# trezor_v1_1.net
KiCad netlist of a schematic drawn in EAGLE
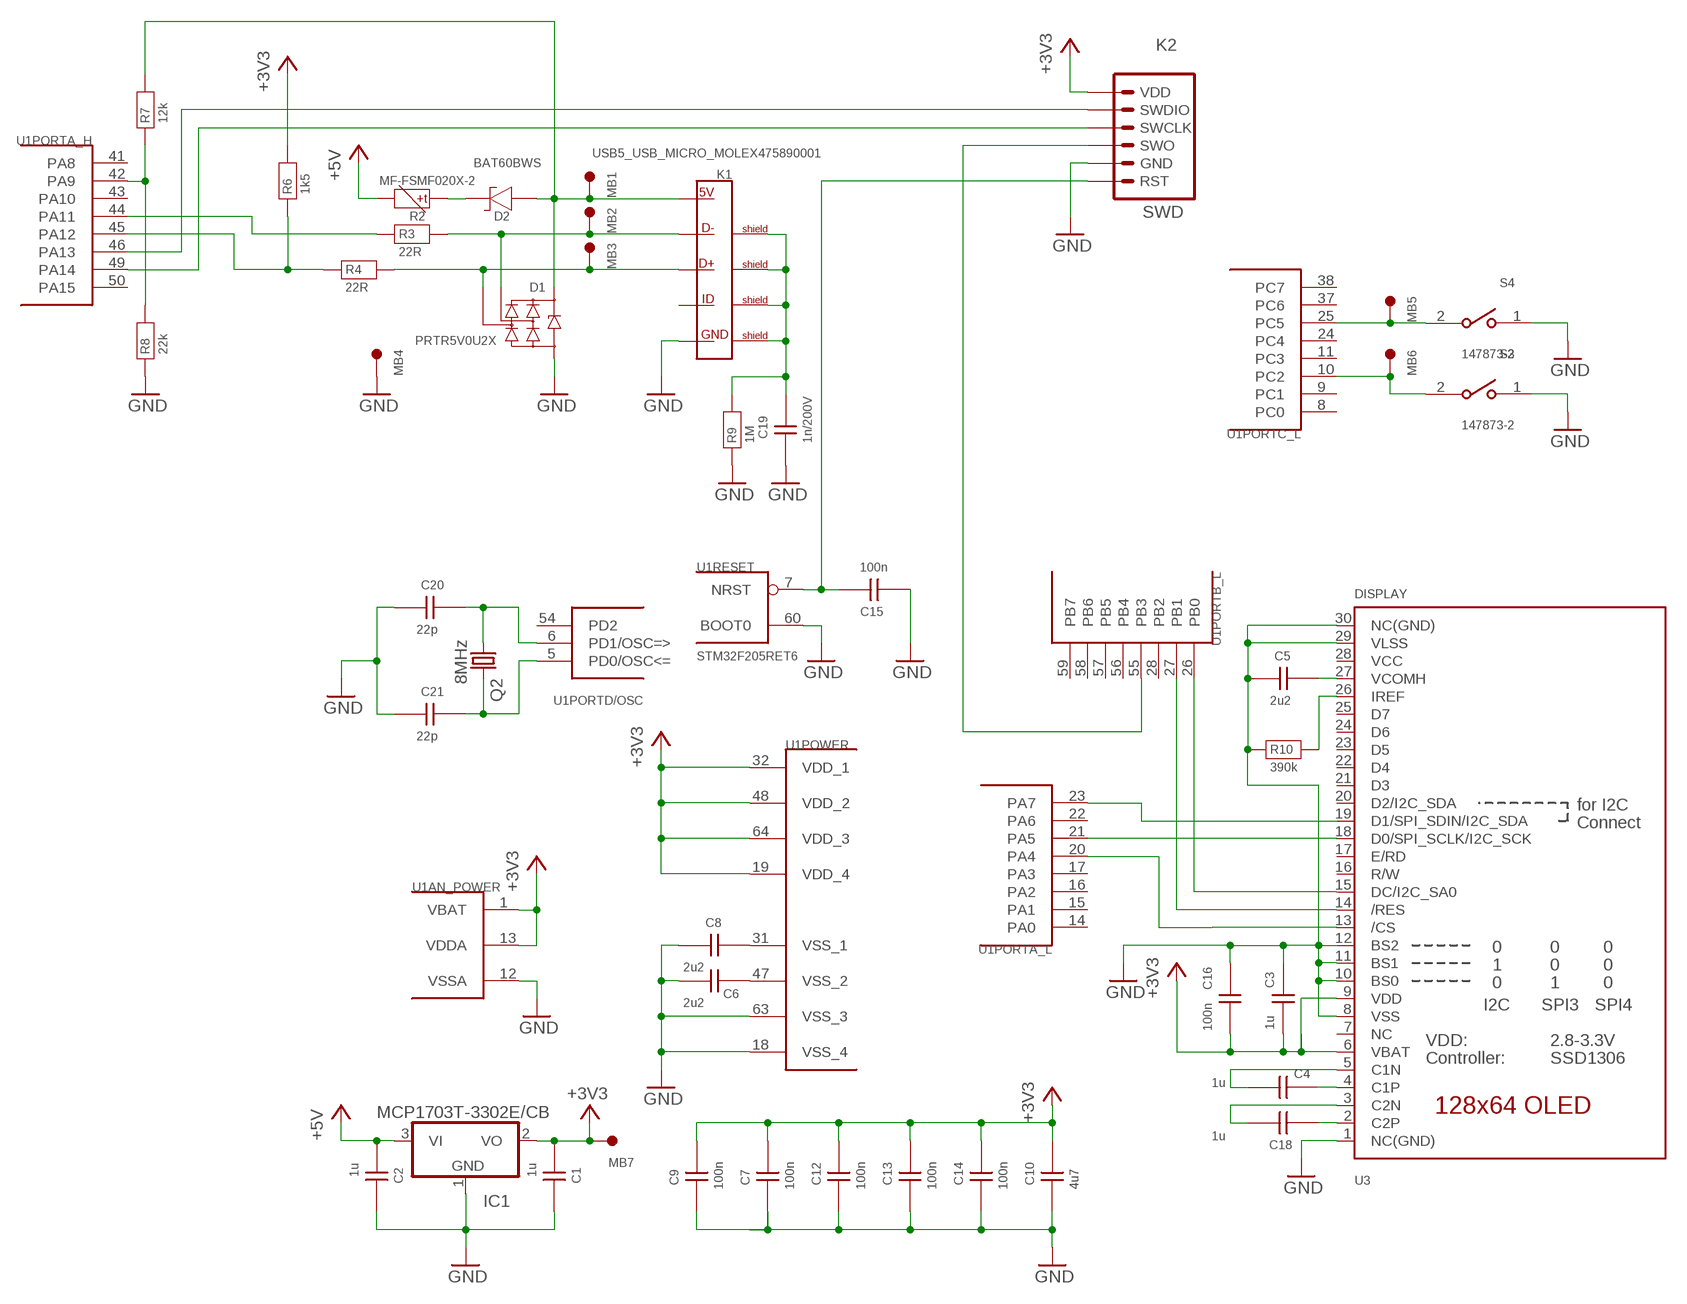
[diagram p0: schematic, sheet 1]

(export (version "E")
  (design (tool "Eeschema 10.0.6"))
  (components
    (comp (ref "C1")
      (value "1u")
      (footprint "eagle-import:0603")
      (libsource (lib "eagle-import") (part "C_0603"))
    )
    (comp (ref "C2")
      (value "1u")
      (footprint "eagle-import:0603")
      (libsource (lib "eagle-import") (part "C_0603"))
    )
    (comp (ref "C3")
      (value "1u")
      (footprint "eagle-import:0603")
      (libsource (lib "eagle-import") (part "C_0603"))
    )
    (comp (ref "C4")
      (value "1u")
      (footprint "eagle-import:0603")
      (libsource (lib "eagle-import") (part "C_0603"))
    )
    (comp (ref "C5")
      (value "2u2")
      (footprint "eagle-import:0603")
      (libsource (lib "eagle-import") (part "C_0603"))
    )
    (comp (ref "C6")
      (value "2u2")
      (footprint "eagle-import:0603")
      (libsource (lib "eagle-import") (part "C_0603"))
    )
    (comp (ref "C7")
      (value "100n")
      (footprint "eagle-import:0603")
      (libsource (lib "eagle-import") (part "C_0603"))
    )
    (comp (ref "C8")
      (value "2u2")
      (footprint "eagle-import:0603")
      (libsource (lib "eagle-import") (part "C_0603"))
    )
    (comp (ref "C9")
      (value "100n")
      (footprint "eagle-import:0603")
      (libsource (lib "eagle-import") (part "C_0603"))
    )
    (comp (ref "C10")
      (value "4u7")
      (footprint "eagle-import:0603")
      (libsource (lib "eagle-import") (part "C_0603"))
    )
    (comp (ref "C12")
      (value "100n")
      (footprint "eagle-import:0603")
      (libsource (lib "eagle-import") (part "C_0603"))
    )
    (comp (ref "C13")
      (value "100n")
      (footprint "eagle-import:0603")
      (libsource (lib "eagle-import") (part "C_0603"))
    )
    (comp (ref "C14")
      (value "100n")
      (footprint "eagle-import:0603")
      (libsource (lib "eagle-import") (part "C_0603"))
    )
    (comp (ref "C15")
      (value "100n")
      (footprint "eagle-import:0603")
      (libsource (lib "eagle-import") (part "C_0603"))
    )
    (comp (ref "C16")
      (value "100n")
      (footprint "eagle-import:0603")
      (libsource (lib "eagle-import") (part "C_0603"))
    )
    (comp (ref "C18")
      (value "1u")
      (footprint "eagle-import:0603")
      (libsource (lib "eagle-import") (part "C_0603"))
    )
    (comp (ref "C19")
      (value "1n/200V")
      (footprint "eagle-import:0603")
      (libsource (lib "eagle-import") (part "C_0603"))
    )
    (comp (ref "C20")
      (value "22p")
      (footprint "eagle-import:0603")
      (libsource (lib "eagle-import") (part "C_0603"))
    )
    (comp (ref "C21")
      (value "22p")
      (footprint "eagle-import:0603")
      (libsource (lib "eagle-import") (part "C_0603"))
    )
    (comp (ref "D1")
      (value "PRTR5V0U2X")
      (footprint "eagle-import:SOT143B")
      (libsource (lib "eagle-import") (part "PRTR5V0_SOT143B"))
    )
    (comp (ref "D2")
      (value "BAT60BWS")
      (footprint "eagle-import:SOD323")
      (libsource (lib "eagle-import") (part "DS_SOD323"))
    )
    (comp (ref "IC1")
      (value "MCP1703T-3302E/CB")
      (footprint "eagle-import:SOT23")
      (libsource (lib "eagle-import") (part "MCP1703CB"))
    )
    (comp (ref "K1")
      (value "USB5_USB_MICRO_MOLEX475890001")
      (footprint "eagle-import:USB_MICRO-MOLEX475890001")
      (libsource (lib "eagle-import") (part "USB5_USB_MICRO_MOLEX475890001"))
    )
    (comp (ref "K2")
      (value "SWD")
      (footprint "eagle-import:SWD")
      (libsource (lib "eagle-import") (part "SWD"))
    )
    (comp (ref "MB1")
      (value "MB_1.50")
      (footprint "eagle-import:MB1.5")
      (libsource (lib "eagle-import") (part "MB_1.50"))
    )
    (comp (ref "MB2")
      (value "MB_1.50")
      (footprint "eagle-import:MB1.5")
      (libsource (lib "eagle-import") (part "MB_1.50"))
    )
    (comp (ref "MB3")
      (value "MB_1.50")
      (footprint "eagle-import:MB1.5")
      (libsource (lib "eagle-import") (part "MB_1.50"))
    )
    (comp (ref "MB4")
      (value "MB_1.50")
      (footprint "eagle-import:MB1.5")
      (libsource (lib "eagle-import") (part "MB_1.50"))
    )
    (comp (ref "MB5")
      (value "MB_1.50")
      (footprint "eagle-import:MB1.5")
      (libsource (lib "eagle-import") (part "MB_1.50"))
    )
    (comp (ref "MB6")
      (value "MB_1.50")
      (footprint "eagle-import:MB1.5")
      (libsource (lib "eagle-import") (part "MB_1.50"))
    )
    (comp (ref "MB7")
      (value "MB_1.50")
      (footprint "eagle-import:MB1.5")
      (libsource (lib "eagle-import") (part "MB_1.50"))
    )
    (comp (ref "Q2")
      (value "8MHz")
      (footprint "eagle-import:CTS406")
      (libsource (lib "eagle-import") (part "CRYSTALCTS406"))
    )
    (comp (ref "R2")
      (value "MF-FSMF020X-2")
      (footprint "eagle-import:0603")
      (libsource (lib "eagle-import") (part "POLYSWITCH_0603"))
    )
    (comp (ref "R3")
      (value "22R")
      (footprint "eagle-import:0603")
      (libsource (lib "eagle-import") (part "R_0603"))
    )
    (comp (ref "R4")
      (value "22R")
      (footprint "eagle-import:0603")
      (libsource (lib "eagle-import") (part "R_0603"))
    )
    (comp (ref "R6")
      (value "1k5")
      (footprint "eagle-import:0603")
      (libsource (lib "eagle-import") (part "R_0603"))
    )
    (comp (ref "R7")
      (value "12k")
      (footprint "eagle-import:0603")
      (libsource (lib "eagle-import") (part "R_0603"))
    )
    (comp (ref "R8")
      (value "22k")
      (footprint "eagle-import:0603")
      (libsource (lib "eagle-import") (part "R_0603"))
    )
    (comp (ref "R9")
      (value "1M")
      (footprint "eagle-import:0603")
      (libsource (lib "eagle-import") (part "R_0603"))
    )
    (comp (ref "R10")
      (value "390k")
      (footprint "eagle-import:0603")
      (libsource (lib "eagle-import") (part "R_0603"))
    )
    (comp (ref "S3")
      (value "147873-2")
      (footprint "eagle-import:SW_147873-2")
      (fields (field (name "MF") "TE Connectivity"))
      (libsource (lib "eagle-import") (part "147873-2"))
    )
    (comp (ref "S4")
      (value "147873-2")
      (footprint "eagle-import:SW_147873-2")
      (fields (field (name "MF") "TE Connectivity"))
      (libsource (lib "eagle-import") (part "147873-2"))
    )
    (comp (ref "U1")
      (value "STM32F205RET6")
      (footprint "eagle-import:TQFP64")
      (libsource (lib "eagle-import") (part "STM32F10XRXT6"))
    )
    (comp (ref "U3")
      (value "DISPLAY")
      (footprint "eagle-import:UG-2864HSWEG01_0.96IN_WRAPAROUND")
      (libsource (lib "eagle-import") (part "DISP_OLED_UG-2864HSWEG010.96{dblquote}"))
    )
  )
  (nets
    (net (code "1") (name "+3V3") (class "Default")
      (node (ref "C1") (pin "1") (pinfunction "1_1") (pintype "passive"))
      (node (ref "C10") (pin "2") (pinfunction "2_2") (pintype "passive"))
      (node (ref "C12") (pin "2") (pinfunction "2_2") (pintype "passive"))
      (node (ref "C13") (pin "2") (pinfunction "2_2") (pintype "passive"))
      (node (ref "C14") (pin "2") (pinfunction "2_2") (pintype "passive"))
      (node (ref "C16") (pin "1") (pinfunction "1_1") (pintype "passive"))
      (node (ref "C3") (pin "1") (pinfunction "1_1") (pintype "passive"))
      (node (ref "C7") (pin "2") (pinfunction "2_2") (pintype "passive"))
      (node (ref "C9") (pin "2") (pinfunction "2_2") (pintype "passive"))
      (node (ref "IC1") (pin "2") (pinfunction "VO_2") (pintype "passive"))
      (node (ref "K2") (pin "6") (pinfunction "VDD_6") (pintype "passive"))
      (node (ref "MB7") (pin "1") (pinfunction "1_1") (pintype "passive"))
      (node (ref "R6") (pin "2") (pinfunction "2_2") (pintype "passive"))
      (node (ref "U1") (pin "1") (pinfunction "VBAT_1") (pintype "power_in"))
      (node (ref "U1") (pin "13") (pinfunction "VDDA_13") (pintype "power_in"))
      (node (ref "U1") (pin "19") (pinfunction "VDD_4_19") (pintype "power_in"))
      (node (ref "U1") (pin "32") (pinfunction "VDD_1_32") (pintype "power_in"))
      (node (ref "U1") (pin "48") (pinfunction "VDD_2_48") (pintype "power_in"))
      (node (ref "U1") (pin "64") (pinfunction "VDD_3_64") (pintype "power_in"))
      (node (ref "U3") (pin "6") (pinfunction "VBAT_6") (pintype "input"))
      (node (ref "U3") (pin "9") (pinfunction "VDD_9") (pintype "power_in"))
    )
    (net (code "2") (name "+5V") (class "Default")
      (node (ref "C2") (pin "1") (pinfunction "1_1") (pintype "passive"))
      (node (ref "IC1") (pin "3") (pinfunction "VI_3") (pintype "input"))
      (node (ref "R2") (pin "2") (pinfunction "2_2") (pintype "passive"))
    )
    (net (code "3") (name "/VCC") (class "Default")
      (node (ref "U3") (pin "28") (pinfunction "VCC_28") (pintype "power_in"))
    )
    (net (code "4") (name "GND") (class "Default")
      (node (ref "C1") (pin "2") (pinfunction "2_2") (pintype "passive"))
      (node (ref "C10") (pin "1") (pinfunction "1_1") (pintype "passive"))
      (node (ref "C12") (pin "1") (pinfunction "1_1") (pintype "passive"))
      (node (ref "C13") (pin "1") (pinfunction "1_1") (pintype "passive"))
      (node (ref "C14") (pin "1") (pinfunction "1_1") (pintype "passive"))
      (node (ref "C15") (pin "1") (pinfunction "1_1") (pintype "passive"))
      (node (ref "C16") (pin "2") (pinfunction "2_2") (pintype "passive"))
      (node (ref "C19") (pin "1") (pinfunction "1_1") (pintype "passive"))
      (node (ref "C2") (pin "2") (pinfunction "2_2") (pintype "passive"))
      (node (ref "C20") (pin "1") (pinfunction "1_1") (pintype "passive"))
      (node (ref "C21") (pin "1") (pinfunction "1_1") (pintype "passive"))
      (node (ref "C3") (pin "2") (pinfunction "2_2") (pintype "passive"))
      (node (ref "C5") (pin "1") (pinfunction "1_1") (pintype "passive"))
      (node (ref "C6") (pin "1") (pinfunction "1_1") (pintype "passive"))
      (node (ref "C7") (pin "1") (pinfunction "1_1") (pintype "passive"))
      (node (ref "C8") (pin "1") (pinfunction "1_1") (pintype "passive"))
      (node (ref "C9") (pin "1") (pinfunction "1_1") (pintype "passive"))
      (node (ref "D1") (pin "1") (pinfunction "GND_1") (pintype "passive"))
      (node (ref "IC1") (pin "1") (pinfunction "GND_1") (pintype "passive"))
      (node (ref "K1") (pin "5") (pinfunction "5_GND_5") (pintype "bidirectional"))
      (node (ref "K2") (pin "2") (pinfunction "GND_2") (pintype "passive"))
      (node (ref "MB4") (pin "1") (pinfunction "1_1") (pintype "passive"))
      (node (ref "R10") (pin "1") (pinfunction "1_1") (pintype "passive"))
      (node (ref "R8") (pin "1") (pinfunction "1_1") (pintype "passive"))
      (node (ref "R9") (pin "1") (pinfunction "1_1") (pintype "passive"))
      (node (ref "S3") (pin "1") (pinfunction "1_1") (pintype "passive"))
      (node (ref "S4") (pin "1") (pinfunction "1_1") (pintype "passive"))
      (node (ref "U1") (pin "12") (pinfunction "VSSA_12") (pintype "power_in"))
      (node (ref "U1") (pin "18") (pinfunction "VSS_4_18") (pintype "power_in"))
      (node (ref "U1") (pin "60") (pinfunction "BOOT0_60") (pintype "input"))
      (node (ref "U1") (pin "63") (pinfunction "VSS_3_63") (pintype "power_in"))
      (node (ref "U3") (pin "1") (pinfunction "NC(GND)_1") (pintype "input"))
      (node (ref "U3") (pin "10") (pinfunction "BS0_10") (pintype "input"))
      (node (ref "U3") (pin "11") (pinfunction "BS1_11") (pintype "input"))
      (node (ref "U3") (pin "12") (pinfunction "BS2_12") (pintype "input"))
      (node (ref "U3") (pin "29") (pinfunction "VLSS_29") (pintype "power_in"))
      (node (ref "U3") (pin "30") (pinfunction "NC(GND)_30") (pintype "input"))
      (node (ref "U3") (pin "8") (pinfunction "VSS_8") (pintype "power_in"))
    )
    (net (code "5") (name "Net-(C19-Pad2)") (class "Default")
      (node (ref "C19") (pin "2") (pinfunction "2_2") (pintype "passive"))
      (node (ref "K1") (pin "S1_BOT") (pinfunction "SHIELD_1_S1_BOT") (pintype "passive"))
      (node (ref "K1") (pin "S1_TOP") (pinfunction "SHIELD_1_S1_TOP") (pintype "passive"))
      (node (ref "K1") (pin "S2_BOT") (pinfunction "SHIELD_2_S2_BOT") (pintype "passive"))
      (node (ref "K1") (pin "S2_TOP") (pinfunction "SHIELD_2_S2_TOP") (pintype "passive"))
      (node (ref "K1") (pin "S3_BOT") (pinfunction "SHIELD_3_S3_BOT") (pintype "passive"))
      (node (ref "K1") (pin "S3_TOP") (pinfunction "SHIELD_3_S3_TOP") (pintype "passive"))
      (node (ref "K1") (pin "S4_BOT") (pinfunction "SHIELD_4_S4_BOT") (pintype "passive"))
      (node (ref "K1") (pin "S4_TOP") (pinfunction "SHIELD_4_S4_TOP") (pintype "passive"))
      (node (ref "K1") (pin "SA") (pinfunction "SHIELD_1_SA") (pintype "passive"))
      (node (ref "K1") (pin "SB") (pinfunction "SHIELD_2_SB") (pintype "passive"))
      (node (ref "R9") (pin "2") (pinfunction "2_2") (pintype "passive"))
    )
    (net (code "6") (name "Net-(D1-I{slash}O1)") (class "Default")
      (node (ref "D1") (pin "2") (pinfunction "I/O1_2") (pintype "passive"))
      (node (ref "K1") (pin "2") (pinfunction "2_D-_2") (pintype "bidirectional"))
      (node (ref "MB2") (pin "1") (pinfunction "1_1") (pintype "passive"))
      (node (ref "R3") (pin "2") (pinfunction "2_2") (pintype "passive"))
    )
    (net (code "7") (name "Net-(D1-I{slash}O2)") (class "Default")
      (node (ref "D1") (pin "3") (pinfunction "I/O2_3") (pintype "passive"))
      (node (ref "K1") (pin "3") (pinfunction "3_D+_3") (pintype "bidirectional"))
      (node (ref "MB3") (pin "1") (pinfunction "1_1") (pintype "passive"))
      (node (ref "R4") (pin "2") (pinfunction "2_2") (pintype "passive"))
    )
    (net (code "8") (name "Net-(D1-VCC)") (class "Default")
      (node (ref "D1") (pin "4") (pinfunction "VCC_4") (pintype "passive"))
      (node (ref "D2") (pin "A") (pinfunction "1_A") (pintype "passive"))
      (node (ref "K1") (pin "1") (pinfunction "1_5V_1") (pintype "bidirectional"))
      (node (ref "MB1") (pin "1") (pinfunction "1_1") (pintype "passive"))
      (node (ref "R7") (pin "2") (pinfunction "2_2") (pintype "passive"))
    )
    (net (code "9") (name "Net-(D2-2)") (class "Default")
      (node (ref "D2") (pin "K") (pinfunction "2_K") (pintype "passive"))
      (node (ref "R2") (pin "1") (pinfunction "1_1") (pintype "passive"))
    )
    (net (code "10") (name "Net-(K2-RST)") (class "Default")
      (node (ref "C15") (pin "2") (pinfunction "2_2") (pintype "passive"))
      (node (ref "K2") (pin "1") (pinfunction "RST_1") (pintype "passive"))
      (node (ref "U1") (pin "7") (pinfunction "NRST_7") (pintype "input"))
    )
    (net (code "11") (name "Net-(K2-SWCLK)") (class "Default")
      (node (ref "K2") (pin "4") (pinfunction "SWCLK_4") (pintype "passive"))
      (node (ref "U1") (pin "49") (pinfunction "PA14_49") (pintype "bidirectional"))
    )
    (net (code "12") (name "Net-(K2-SWDIO)") (class "Default")
      (node (ref "K2") (pin "5") (pinfunction "SWDIO_5") (pintype "passive"))
      (node (ref "U1") (pin "46") (pinfunction "PA13_46") (pintype "bidirectional"))
    )
    (net (code "13") (name "Net-(K2-SWO)") (class "Default")
      (node (ref "K2") (pin "3") (pinfunction "SWO_3") (pintype "passive"))
      (node (ref "U1") (pin "55") (pinfunction "PB3_55") (pintype "bidirectional"))
    )
    (net (code "14") (name "Net-(Q2-2)") (class "Default")
      (node (ref "C21") (pin "2") (pinfunction "2_2") (pintype "passive"))
      (node (ref "Q2") (pin "3") (pinfunction "2_3") (pintype "passive"))
      (node (ref "U1") (pin "5") (pinfunction "PD0/OSC<=_5") (pintype "bidirectional"))
    )
    (net (code "15") (name "Net-(U1B-PA9)") (class "Default")
      (node (ref "R7") (pin "1") (pinfunction "1_1") (pintype "passive"))
      (node (ref "R8") (pin "2") (pinfunction "2_2") (pintype "passive"))
      (node (ref "U1") (pin "42") (pinfunction "PA9_42") (pintype "bidirectional"))
    )
    (net (code "16") (name "Net-(U1B-PA11)") (class "Default")
      (node (ref "R3") (pin "1") (pinfunction "1_1") (pintype "passive"))
      (node (ref "U1") (pin "44") (pinfunction "PA11_44") (pintype "bidirectional"))
    )
    (net (code "17") (name "Net-(U1B-PA12)") (class "Default")
      (node (ref "R4") (pin "1") (pinfunction "1_1") (pintype "passive"))
      (node (ref "R6") (pin "1") (pinfunction "1_1") (pintype "passive"))
      (node (ref "U1") (pin "45") (pinfunction "PA12_45") (pintype "bidirectional"))
    )
    (net (code "18") (name "Net-(U1C-PA4)") (class "Default")
      (node (ref "U1") (pin "20") (pinfunction "PA4_20") (pintype "bidirectional"))
      (node (ref "U3") (pin "13") (pinfunction "/CS_13") (pintype "input"))
    )
    (net (code "19") (name "Net-(U1C-PA5)") (class "Default")
      (node (ref "U1") (pin "21") (pinfunction "PA5_21") (pintype "bidirectional"))
      (node (ref "U3") (pin "18") (pinfunction "D0/SPI_SCLK/I2C_SCK_18") (pintype "bidirectional"))
    )
    (net (code "20") (name "Net-(U1C-PA7)") (class "Default")
      (node (ref "U1") (pin "23") (pinfunction "PA7_23") (pintype "bidirectional"))
      (node (ref "U3") (pin "19") (pinfunction "D1/SPI_SDIN/I2C_SDA_19") (pintype "bidirectional"))
    )
    (net (code "21") (name "Net-(U1E-PB0)") (class "Default")
      (node (ref "U1") (pin "26") (pinfunction "PB0_26") (pintype "bidirectional"))
      (node (ref "U3") (pin "15") (pinfunction "DC/I2C_SA0_15") (pintype "input"))
    )
    (net (code "22") (name "Net-(U1E-PB1)") (class "Default")
      (node (ref "U1") (pin "27") (pinfunction "PB1_27") (pintype "bidirectional"))
      (node (ref "U3") (pin "14") (pinfunction "/RES_14") (pintype "input"))
    )
    (net (code "23") (name "Net-(U1G-PC2)") (class "Default")
      (node (ref "MB6") (pin "1") (pinfunction "1_1") (pintype "passive"))
      (node (ref "S3") (pin "2") (pinfunction "2_2") (pintype "passive"))
      (node (ref "U1") (pin "10") (pinfunction "PC2_10") (pintype "bidirectional"))
    )
    (net (code "24") (name "Net-(U1G-PC5)") (class "Default")
      (node (ref "MB5") (pin "1") (pinfunction "1_1") (pintype "passive"))
      (node (ref "S4") (pin "2") (pinfunction "2_2") (pintype "passive"))
      (node (ref "U1") (pin "25") (pinfunction "PC5_25") (pintype "bidirectional"))
    )
    (net (code "25") (name "Net-(U1H-PD1{slash}OSC=>)") (class "Default")
      (node (ref "C20") (pin "2") (pinfunction "2_2") (pintype "passive"))
      (node (ref "Q2") (pin "1") (pinfunction "1_1") (pintype "passive"))
      (node (ref "U1") (pin "6") (pinfunction "PD1/OSC=>_6") (pintype "bidirectional"))
    )
    (net (code "26") (name "Net-(U1I-VSS_1)") (class "Default")
      (node (ref "C8") (pin "2") (pinfunction "2_2") (pintype "passive"))
      (node (ref "U1") (pin "31") (pinfunction "VSS_1_31") (pintype "power_in"))
    )
    (net (code "27") (name "Net-(U1I-VSS_2)") (class "Default")
      (node (ref "C6") (pin "2") (pinfunction "2_2") (pintype "passive"))
      (node (ref "U1") (pin "47") (pinfunction "VSS_2_47") (pintype "power_in"))
    )
    (net (code "28") (name "Net-(U3-C1N)") (class "Default")
      (node (ref "C4") (pin "2") (pinfunction "2_2") (pintype "passive"))
      (node (ref "U3") (pin "5") (pinfunction "C1N_5") (pintype "input"))
    )
    (net (code "29") (name "Net-(U3-C1P)") (class "Default")
      (node (ref "C4") (pin "1") (pinfunction "1_1") (pintype "passive"))
      (node (ref "U3") (pin "4") (pinfunction "C1P_4") (pintype "input"))
    )
    (net (code "30") (name "Net-(U3-C2N)") (class "Default")
      (node (ref "C18") (pin "2") (pinfunction "2_2") (pintype "passive"))
      (node (ref "U3") (pin "3") (pinfunction "C2N_3") (pintype "input"))
    )
    (net (code "31") (name "Net-(U3-C2P)") (class "Default")
      (node (ref "C18") (pin "1") (pinfunction "1_1") (pintype "passive"))
      (node (ref "U3") (pin "2") (pinfunction "C2P_2") (pintype "input"))
    )
    (net (code "32") (name "Net-(U3-IREF)") (class "Default")
      (node (ref "R10") (pin "2") (pinfunction "2_2") (pintype "passive"))
      (node (ref "U3") (pin "26") (pinfunction "IREF_26") (pintype "input"))
    )
    (net (code "33") (name "Net-(U3-VCOMH)") (class "Default")
      (node (ref "C5") (pin "2") (pinfunction "2_2") (pintype "passive"))
      (node (ref "U3") (pin "27") (pinfunction "VCOMH_27") (pintype "output"))
    )
    (net (code "34") (name "unconnected-(K1-4_ID-Pad4)") (class "Default")
      (node (ref "K1") (pin "4") (pinfunction "4_ID_4") (pintype "bidirectional"))
    )
    (net (code "35") (name "unconnected-(U1B-PA8-Pad41)") (class "Default")
      (node (ref "U1") (pin "41") (pinfunction "PA8_41") (pintype "bidirectional"))
    )
    (net (code "36") (name "unconnected-(U1B-PA10-Pad43)") (class "Default")
      (node (ref "U1") (pin "43") (pinfunction "PA10_43") (pintype "bidirectional"))
    )
    (net (code "37") (name "unconnected-(U1B-PA15-Pad50)") (class "Default")
      (node (ref "U1") (pin "50") (pinfunction "PA15_50") (pintype "bidirectional"))
    )
    (net (code "38") (name "unconnected-(U1C-PA0-Pad14)") (class "Default")
      (node (ref "U1") (pin "14") (pinfunction "PA0_14") (pintype "bidirectional"))
    )
    (net (code "39") (name "unconnected-(U1C-PA1-Pad15)") (class "Default")
      (node (ref "U1") (pin "15") (pinfunction "PA1_15") (pintype "bidirectional"))
    )
    (net (code "40") (name "unconnected-(U1C-PA2-Pad16)") (class "Default")
      (node (ref "U1") (pin "16") (pinfunction "PA2_16") (pintype "bidirectional"))
    )
    (net (code "41") (name "unconnected-(U1C-PA3-Pad17)") (class "Default")
      (node (ref "U1") (pin "17") (pinfunction "PA3_17") (pintype "bidirectional"))
    )
    (net (code "42") (name "unconnected-(U1C-PA6-Pad22)") (class "Default")
      (node (ref "U1") (pin "22") (pinfunction "PA6_22") (pintype "bidirectional"))
    )
    (net (code "43") (name "unconnected-(U1E-PB2-Pad28)") (class "Default")
      (node (ref "U1") (pin "28") (pinfunction "PB2_28") (pintype "bidirectional"))
    )
    (net (code "44") (name "unconnected-(U1E-PB4-Pad56)") (class "Default")
      (node (ref "U1") (pin "56") (pinfunction "PB4_56") (pintype "bidirectional"))
    )
    (net (code "45") (name "unconnected-(U1E-PB5-Pad57)") (class "Default")
      (node (ref "U1") (pin "57") (pinfunction "PB5_57") (pintype "bidirectional"))
    )
    (net (code "46") (name "unconnected-(U1E-PB6-Pad58)") (class "Default")
      (node (ref "U1") (pin "58") (pinfunction "PB6_58") (pintype "bidirectional"))
    )
    (net (code "47") (name "unconnected-(U1E-PB7-Pad59)") (class "Default")
      (node (ref "U1") (pin "59") (pinfunction "PB7_59") (pintype "bidirectional"))
    )
    (net (code "48") (name "unconnected-(U1G-PC0-Pad8)") (class "Default")
      (node (ref "U1") (pin "8") (pinfunction "PC0_8") (pintype "bidirectional"))
    )
    (net (code "49") (name "unconnected-(U1G-PC1-Pad9)") (class "Default")
      (node (ref "U1") (pin "9") (pinfunction "PC1_9") (pintype "bidirectional"))
    )
    (net (code "50") (name "unconnected-(U1G-PC3-Pad11)") (class "Default")
      (node (ref "U1") (pin "11") (pinfunction "PC3_11") (pintype "bidirectional"))
    )
    (net (code "51") (name "unconnected-(U1G-PC4-Pad24)") (class "Default")
      (node (ref "U1") (pin "24") (pinfunction "PC4_24") (pintype "bidirectional"))
    )
    (net (code "52") (name "unconnected-(U1G-PC6-Pad37)") (class "Default")
      (node (ref "U1") (pin "37") (pinfunction "PC6_37") (pintype "bidirectional"))
    )
    (net (code "53") (name "unconnected-(U1G-PC7-Pad38)") (class "Default")
      (node (ref "U1") (pin "38") (pinfunction "PC7_38") (pintype "bidirectional"))
    )
    (net (code "54") (name "unconnected-(U1H-PD2-Pad54)") (class "Default")
      (node (ref "U1") (pin "54") (pinfunction "PD2_54") (pintype "bidirectional"))
    )
    (net (code "55") (name "unconnected-(U3-D2{slash}I2C_SDA-Pad20)") (class "Default")
      (node (ref "U3") (pin "20") (pinfunction "D2/I2C_SDA_20") (pintype "bidirectional"))
    )
    (net (code "56") (name "unconnected-(U3-D3-Pad21)") (class "Default")
      (node (ref "U3") (pin "21") (pinfunction "D3_21") (pintype "bidirectional"))
    )
    (net (code "57") (name "unconnected-(U3-D4-Pad22)") (class "Default")
      (node (ref "U3") (pin "22") (pinfunction "D4_22") (pintype "bidirectional"))
    )
    (net (code "58") (name "unconnected-(U3-D5-Pad23)") (class "Default")
      (node (ref "U3") (pin "23") (pinfunction "D5_23") (pintype "bidirectional"))
    )
    (net (code "59") (name "unconnected-(U3-D6-Pad24)") (class "Default")
      (node (ref "U3") (pin "24") (pinfunction "D6_24") (pintype "bidirectional"))
    )
    (net (code "60") (name "unconnected-(U3-D7-Pad25)") (class "Default")
      (node (ref "U3") (pin "25") (pinfunction "D7_25") (pintype "bidirectional"))
    )
    (net (code "61") (name "unconnected-(U3-E{slash}RD-Pad17)") (class "Default")
      (node (ref "U3") (pin "17") (pinfunction "E/RD_17") (pintype "input"))
    )
    (net (code "62") (name "unconnected-(U3-NC-Pad7)") (class "Default")
      (node (ref "U3") (pin "7") (pinfunction "NC_7") (pintype "no_connect"))
    )
    (net (code "63") (name "unconnected-(U3-R{slash}W-Pad16)") (class "Default")
      (node (ref "U3") (pin "16") (pinfunction "R/W_16") (pintype "input"))
    )
  )
)
